# 5_64MB_SDRAM.net
KiCad netlist of a schematic drawn in Altium Designer
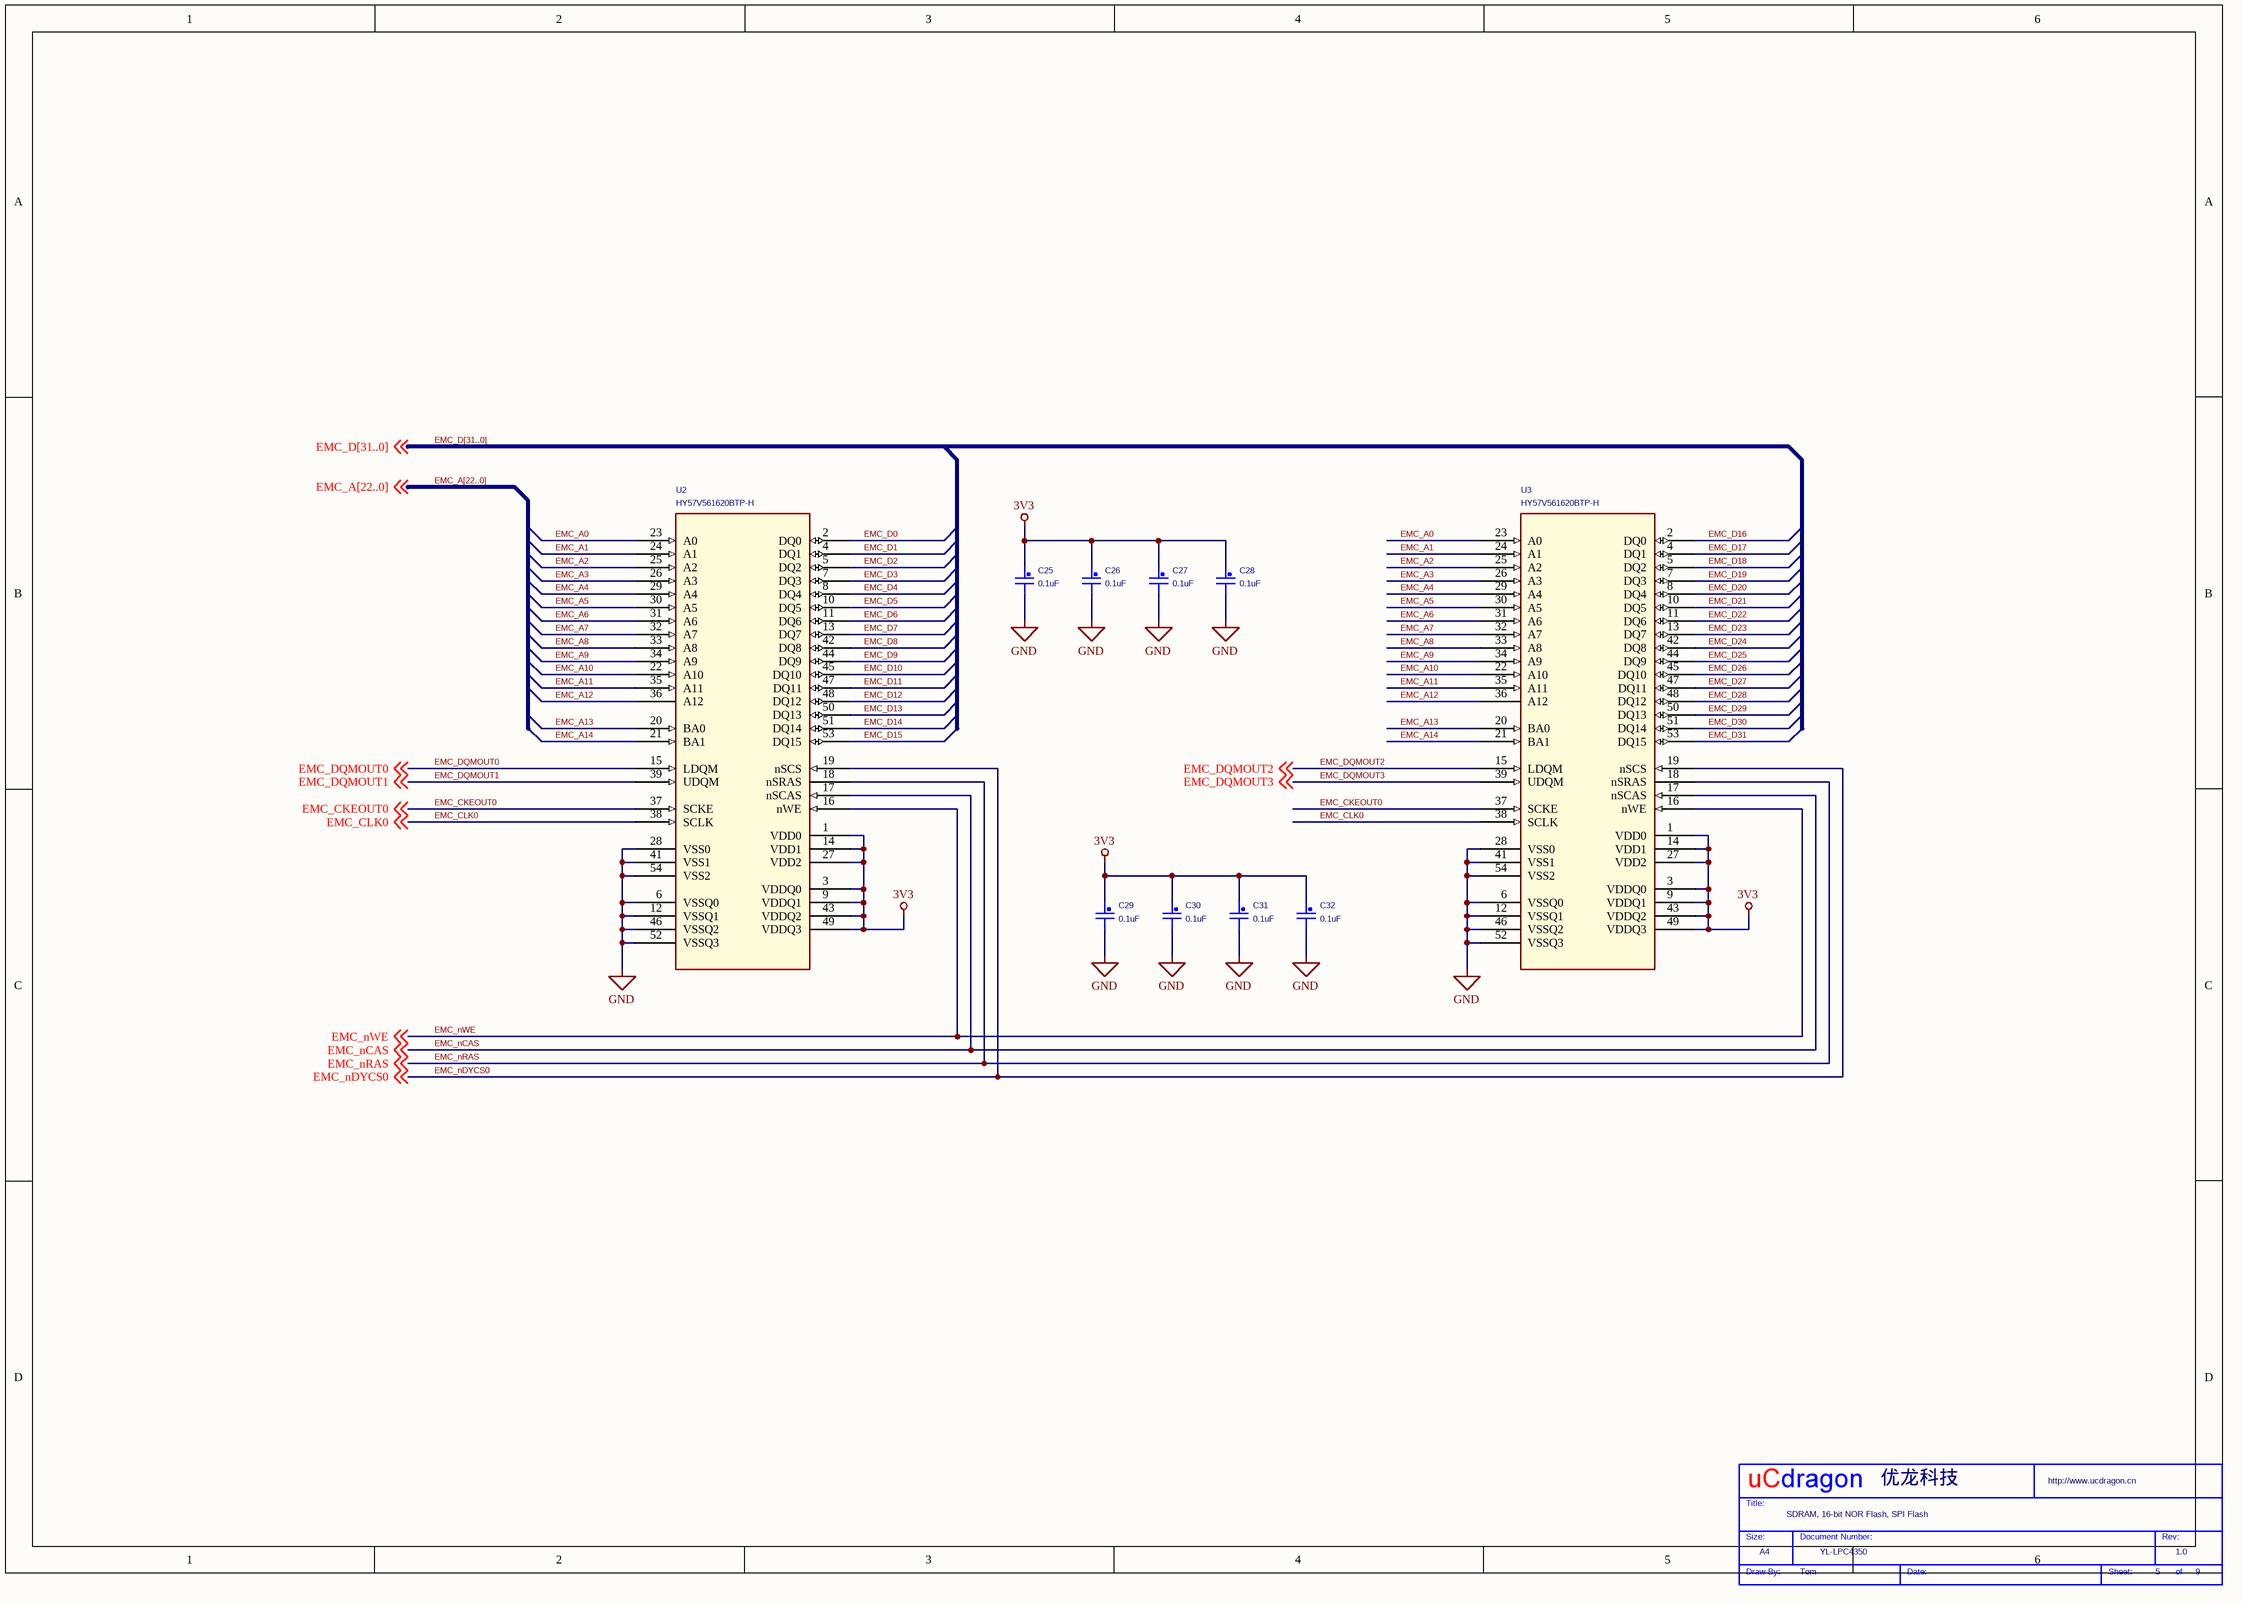
[diagram p0: 5) 64MB SDRAM.SchDoc]

(export (version "E")
  (design (tool "Eeschema 10.0.6"))
  (components
    (comp (ref "C25")
      (value "0.1uF")
      (footprint "CAP0805")
      (fields (field (name "VOLTAGE") "16V"))
      (libsource (lib "*") (part "C_Generic"))
    )
    (comp (ref "C26")
      (value "0.1uF")
      (footprint "CAP0805")
      (fields (field (name "VOLTAGE") "16V"))
      (libsource (lib "*") (part "C_Generic"))
    )
    (comp (ref "C27")
      (value "0.1uF")
      (footprint "CAP0805")
      (fields (field (name "VOLTAGE") "16V"))
      (libsource (lib "*") (part "C_Generic"))
    )
    (comp (ref "C28")
      (value "0.1uF")
      (footprint "CAP0805")
      (fields (field (name "VOLTAGE") "16V"))
      (libsource (lib "*") (part "C_Generic"))
    )
    (comp (ref "C29")
      (value "0.1uF")
      (footprint "CAP0805")
      (fields (field (name "VOLTAGE") "16V"))
      (libsource (lib "*") (part "C_Generic"))
    )
    (comp (ref "C30")
      (value "0.1uF")
      (footprint "CAP0805")
      (fields (field (name "VOLTAGE") "16V"))
      (libsource (lib "*") (part "C_Generic"))
    )
    (comp (ref "C31")
      (value "0.1uF")
      (footprint "CAP0805")
      (fields (field (name "VOLTAGE") "16V"))
      (libsource (lib "*") (part "C_Generic"))
    )
    (comp (ref "C32")
      (value "0.1uF")
      (footprint "CAP0805")
      (fields (field (name "VOLTAGE") "16V"))
      (libsource (lib "*") (part "C_Generic"))
    )
    (comp (ref "U2") (value "HY57V561620BTP-H") (libsource (lib "*") (part "K4S561632C")))
    (comp (ref "U3") (value "HY57V561620BTP-H") (libsource (lib "*") (part "K4S561632C")))
  )
  (nets
    (net (code "1") (name "3V3") (class "Default")
      (node (ref "C25") (pin "1") (pinfunction "1_1") (pintype "passive"))
      (node (ref "C26") (pin "1") (pinfunction "1_1") (pintype "passive"))
      (node (ref "C27") (pin "1") (pinfunction "1_1") (pintype "passive"))
      (node (ref "C28") (pin "1") (pinfunction "1_1") (pintype "passive"))
      (node (ref "C29") (pin "1") (pinfunction "1_1") (pintype "passive"))
      (node (ref "C30") (pin "1") (pinfunction "1_1") (pintype "passive"))
      (node (ref "C31") (pin "1") (pinfunction "1_1") (pintype "passive"))
      (node (ref "C32") (pin "1") (pinfunction "1_1") (pintype "passive"))
      (node (ref "U2") (pin "1") (pinfunction "VDD0_1") (pintype "power_in"))
      (node (ref "U2") (pin "14") (pinfunction "VDD1_14") (pintype "power_in"))
      (node (ref "U2") (pin "27") (pinfunction "VDD2_27") (pintype "power_in"))
      (node (ref "U2") (pin "3") (pinfunction "VDDQ0_3") (pintype "power_in"))
      (node (ref "U2") (pin "43") (pinfunction "VDDQ2_43") (pintype "power_in"))
      (node (ref "U2") (pin "49") (pinfunction "VDDQ3_49") (pintype "power_in"))
      (node (ref "U2") (pin "9") (pinfunction "VDDQ1_9") (pintype "power_in"))
      (node (ref "U3") (pin "1") (pinfunction "VDD0_1") (pintype "power_in"))
      (node (ref "U3") (pin "14") (pinfunction "VDD1_14") (pintype "power_in"))
      (node (ref "U3") (pin "27") (pinfunction "VDD2_27") (pintype "power_in"))
      (node (ref "U3") (pin "3") (pinfunction "VDDQ0_3") (pintype "power_in"))
      (node (ref "U3") (pin "43") (pinfunction "VDDQ2_43") (pintype "power_in"))
      (node (ref "U3") (pin "49") (pinfunction "VDDQ3_49") (pintype "power_in"))
      (node (ref "U3") (pin "9") (pinfunction "VDDQ1_9") (pintype "power_in"))
    )
    (net (code "2") (name "EMC_A0") (class "Default")
      (node (ref "U2") (pin "23") (pinfunction "A0_23") (pintype "input"))
      (node (ref "U3") (pin "23") (pinfunction "A0_23") (pintype "input"))
    )
    (net (code "3") (name "EMC_A1") (class "Default")
      (node (ref "U2") (pin "24") (pinfunction "A1_24") (pintype "input"))
      (node (ref "U3") (pin "24") (pinfunction "A1_24") (pintype "input"))
    )
    (net (code "4") (name "EMC_A2") (class "Default")
      (node (ref "U2") (pin "25") (pinfunction "A2_25") (pintype "input"))
      (node (ref "U3") (pin "25") (pinfunction "A2_25") (pintype "input"))
    )
    (net (code "5") (name "EMC_A3") (class "Default")
      (node (ref "U2") (pin "26") (pinfunction "A3_26") (pintype "input"))
      (node (ref "U3") (pin "26") (pinfunction "A3_26") (pintype "input"))
    )
    (net (code "6") (name "EMC_A4") (class "Default")
      (node (ref "U2") (pin "29") (pinfunction "A4_29") (pintype "input"))
      (node (ref "U3") (pin "29") (pinfunction "A4_29") (pintype "input"))
    )
    (net (code "7") (name "EMC_A5") (class "Default")
      (node (ref "U2") (pin "30") (pinfunction "A5_30") (pintype "input"))
      (node (ref "U3") (pin "30") (pinfunction "A5_30") (pintype "input"))
    )
    (net (code "8") (name "EMC_A6") (class "Default")
      (node (ref "U2") (pin "31") (pinfunction "A6_31") (pintype "input"))
      (node (ref "U3") (pin "31") (pinfunction "A6_31") (pintype "input"))
    )
    (net (code "9") (name "EMC_A7") (class "Default")
      (node (ref "U2") (pin "32") (pinfunction "A7_32") (pintype "input"))
      (node (ref "U3") (pin "32") (pinfunction "A7_32") (pintype "input"))
    )
    (net (code "10") (name "EMC_A8") (class "Default")
      (node (ref "U2") (pin "33") (pinfunction "A8_33") (pintype "input"))
      (node (ref "U3") (pin "33") (pinfunction "A8_33") (pintype "input"))
    )
    (net (code "11") (name "EMC_A9") (class "Default")
      (node (ref "U2") (pin "34") (pinfunction "A9_34") (pintype "input"))
      (node (ref "U3") (pin "34") (pinfunction "A9_34") (pintype "input"))
    )
    (net (code "12") (name "EMC_A10") (class "Default")
      (node (ref "U2") (pin "22") (pinfunction "A10_22") (pintype "input"))
      (node (ref "U3") (pin "22") (pinfunction "A10_22") (pintype "input"))
    )
    (net (code "13") (name "EMC_A11") (class "Default")
      (node (ref "U2") (pin "35") (pinfunction "A11_35") (pintype "input"))
      (node (ref "U3") (pin "35") (pinfunction "A11_35") (pintype "input"))
    )
    (net (code "14") (name "EMC_A12") (class "Default")
      (node (ref "U2") (pin "36") (pinfunction "A12_36") (pintype "passive"))
      (node (ref "U3") (pin "36") (pinfunction "A12_36") (pintype "passive"))
    )
    (net (code "15") (name "EMC_A13") (class "Default")
      (node (ref "U2") (pin "20") (pinfunction "BA0_20") (pintype "input"))
      (node (ref "U3") (pin "20") (pinfunction "BA0_20") (pintype "input"))
    )
    (net (code "16") (name "EMC_A14") (class "Default")
      (node (ref "U2") (pin "21") (pinfunction "BA1_21") (pintype "input"))
      (node (ref "U3") (pin "21") (pinfunction "BA1_21") (pintype "input"))
    )
    (net (code "18") (name "EMC_CKEOUT0") (class "Default")
      (node (ref "U2") (pin "37") (pinfunction "SCKE_37") (pintype "input"))
      (node (ref "U3") (pin "37") (pinfunction "SCKE_37") (pintype "input"))
    )
    (net (code "19") (name "EMC_CLK0") (class "Default")
      (node (ref "U2") (pin "38") (pinfunction "SCLK_38") (pintype "input"))
      (node (ref "U3") (pin "38") (pinfunction "SCLK_38") (pintype "input"))
    )
    (net (code "20") (name "EMC_D0") (class "Default")
      (node (ref "U2") (pin "2") (pinfunction "DQ0_2") (pintype "bidirectional"))
    )
    (net (code "21") (name "EMC_D1") (class "Default")
      (node (ref "U2") (pin "4") (pinfunction "DQ1_4") (pintype "bidirectional"))
    )
    (net (code "22") (name "EMC_D2") (class "Default")
      (node (ref "U2") (pin "5") (pinfunction "DQ2_5") (pintype "bidirectional"))
    )
    (net (code "23") (name "EMC_D3") (class "Default")
      (node (ref "U2") (pin "7") (pinfunction "DQ3_7") (pintype "bidirectional"))
    )
    (net (code "24") (name "EMC_D4") (class "Default")
      (node (ref "U2") (pin "8") (pinfunction "DQ4_8") (pintype "bidirectional"))
    )
    (net (code "25") (name "EMC_D5") (class "Default")
      (node (ref "U2") (pin "10") (pinfunction "DQ5_10") (pintype "bidirectional"))
    )
    (net (code "26") (name "EMC_D6") (class "Default")
      (node (ref "U2") (pin "11") (pinfunction "DQ6_11") (pintype "bidirectional"))
    )
    (net (code "27") (name "EMC_D7") (class "Default")
      (node (ref "U2") (pin "13") (pinfunction "DQ7_13") (pintype "bidirectional"))
    )
    (net (code "28") (name "EMC_D8") (class "Default")
      (node (ref "U2") (pin "42") (pinfunction "DQ8_42") (pintype "bidirectional"))
    )
    (net (code "29") (name "EMC_D9") (class "Default")
      (node (ref "U2") (pin "44") (pinfunction "DQ9_44") (pintype "bidirectional"))
    )
    (net (code "30") (name "EMC_D10") (class "Default")
      (node (ref "U2") (pin "45") (pinfunction "DQ10_45") (pintype "bidirectional"))
    )
    (net (code "31") (name "EMC_D11") (class "Default")
      (node (ref "U2") (pin "47") (pinfunction "DQ11_47") (pintype "bidirectional"))
    )
    (net (code "32") (name "EMC_D12") (class "Default")
      (node (ref "U2") (pin "48") (pinfunction "DQ12_48") (pintype "bidirectional"))
    )
    (net (code "33") (name "EMC_D13") (class "Default")
      (node (ref "U2") (pin "50") (pinfunction "DQ13_50") (pintype "bidirectional"))
    )
    (net (code "34") (name "EMC_D14") (class "Default")
      (node (ref "U2") (pin "51") (pinfunction "DQ14_51") (pintype "bidirectional"))
    )
    (net (code "35") (name "EMC_D15") (class "Default")
      (node (ref "U2") (pin "53") (pinfunction "DQ15_53") (pintype "bidirectional"))
    )
    (net (code "36") (name "EMC_D16") (class "Default")
      (node (ref "U3") (pin "2") (pinfunction "DQ0_2") (pintype "bidirectional"))
    )
    (net (code "37") (name "EMC_D17") (class "Default")
      (node (ref "U3") (pin "4") (pinfunction "DQ1_4") (pintype "bidirectional"))
    )
    (net (code "38") (name "EMC_D18") (class "Default")
      (node (ref "U3") (pin "5") (pinfunction "DQ2_5") (pintype "bidirectional"))
    )
    (net (code "39") (name "EMC_D19") (class "Default")
      (node (ref "U3") (pin "7") (pinfunction "DQ3_7") (pintype "bidirectional"))
    )
    (net (code "40") (name "EMC_D20") (class "Default")
      (node (ref "U3") (pin "8") (pinfunction "DQ4_8") (pintype "bidirectional"))
    )
    (net (code "41") (name "EMC_D21") (class "Default")
      (node (ref "U3") (pin "10") (pinfunction "DQ5_10") (pintype "bidirectional"))
    )
    (net (code "42") (name "EMC_D22") (class "Default")
      (node (ref "U3") (pin "11") (pinfunction "DQ6_11") (pintype "bidirectional"))
    )
    (net (code "43") (name "EMC_D23") (class "Default")
      (node (ref "U3") (pin "13") (pinfunction "DQ7_13") (pintype "bidirectional"))
    )
    (net (code "44") (name "EMC_D24") (class "Default")
      (node (ref "U3") (pin "42") (pinfunction "DQ8_42") (pintype "bidirectional"))
    )
    (net (code "45") (name "EMC_D25") (class "Default")
      (node (ref "U3") (pin "44") (pinfunction "DQ9_44") (pintype "bidirectional"))
    )
    (net (code "46") (name "EMC_D26") (class "Default")
      (node (ref "U3") (pin "45") (pinfunction "DQ10_45") (pintype "bidirectional"))
    )
    (net (code "47") (name "EMC_D27") (class "Default")
      (node (ref "U3") (pin "47") (pinfunction "DQ11_47") (pintype "bidirectional"))
    )
    (net (code "48") (name "EMC_D28") (class "Default")
      (node (ref "U3") (pin "48") (pinfunction "DQ12_48") (pintype "bidirectional"))
    )
    (net (code "49") (name "EMC_D29") (class "Default")
      (node (ref "U3") (pin "50") (pinfunction "DQ13_50") (pintype "bidirectional"))
    )
    (net (code "50") (name "EMC_D30") (class "Default")
      (node (ref "U3") (pin "51") (pinfunction "DQ14_51") (pintype "bidirectional"))
    )
    (net (code "51") (name "EMC_D31") (class "Default")
      (node (ref "U3") (pin "53") (pinfunction "DQ15_53") (pintype "bidirectional"))
    )
    (net (code "52") (name "EMC_DQMOUT0") (class "Default")
      (node (ref "U2") (pin "15") (pinfunction "LDQM_15") (pintype "input"))
    )
    (net (code "53") (name "EMC_DQMOUT1") (class "Default")
      (node (ref "U2") (pin "39") (pinfunction "UDQM_39") (pintype "input"))
    )
    (net (code "54") (name "EMC_DQMOUT2") (class "Default")
      (node (ref "U3") (pin "15") (pinfunction "LDQM_15") (pintype "input"))
    )
    (net (code "55") (name "EMC_DQMOUT3") (class "Default")
      (node (ref "U3") (pin "39") (pinfunction "UDQM_39") (pintype "input"))
    )
    (net (code "57") (name "EMC_nCAS") (class "Default")
      (node (ref "U2") (pin "17") (pinfunction "nSCAS_17") (pintype "input"))
      (node (ref "U3") (pin "17") (pinfunction "nSCAS_17") (pintype "input"))
    )
    (net (code "58") (name "EMC_nDYCS0") (class "Default")
      (node (ref "U2") (pin "19") (pinfunction "nSCS_19") (pintype "input"))
      (node (ref "U3") (pin "19") (pinfunction "nSCS_19") (pintype "input"))
    )
    (net (code "59") (name "EMC_nRAS") (class "Default")
      (node (ref "U2") (pin "18") (pinfunction "nSRAS_18") (pintype "passive"))
      (node (ref "U3") (pin "18") (pinfunction "nSRAS_18") (pintype "passive"))
    )
    (net (code "60") (name "EMC_nWE") (class "Default")
      (node (ref "U2") (pin "16") (pinfunction "nWE_16") (pintype "input"))
      (node (ref "U3") (pin "16") (pinfunction "nWE_16") (pintype "input"))
    )
    (net (code "61") (name "GND") (class "Default")
      (node (ref "C25") (pin "2") (pinfunction "2_2") (pintype "passive"))
      (node (ref "C26") (pin "2") (pinfunction "2_2") (pintype "passive"))
      (node (ref "C27") (pin "2") (pinfunction "2_2") (pintype "passive"))
      (node (ref "C28") (pin "2") (pinfunction "2_2") (pintype "passive"))
      (node (ref "C29") (pin "2") (pinfunction "2_2") (pintype "passive"))
      (node (ref "C30") (pin "2") (pinfunction "2_2") (pintype "passive"))
      (node (ref "C31") (pin "2") (pinfunction "2_2") (pintype "passive"))
      (node (ref "C32") (pin "2") (pinfunction "2_2") (pintype "passive"))
      (node (ref "U2") (pin "12") (pinfunction "VSSQ1_12") (pintype "power_in"))
      (node (ref "U2") (pin "28") (pinfunction "VSS0_28") (pintype "power_in"))
      (node (ref "U2") (pin "41") (pinfunction "VSS1_41") (pintype "power_in"))
      (node (ref "U2") (pin "46") (pinfunction "VSSQ2_46") (pintype "power_in"))
      (node (ref "U2") (pin "52") (pinfunction "VSSQ3_52") (pintype "power_in"))
      (node (ref "U2") (pin "54") (pinfunction "VSS2_54") (pintype "power_in"))
      (node (ref "U2") (pin "6") (pinfunction "VSSQ0_6") (pintype "power_in"))
      (node (ref "U3") (pin "12") (pinfunction "VSSQ1_12") (pintype "power_in"))
      (node (ref "U3") (pin "28") (pinfunction "VSS0_28") (pintype "power_in"))
      (node (ref "U3") (pin "41") (pinfunction "VSS1_41") (pintype "power_in"))
      (node (ref "U3") (pin "46") (pinfunction "VSSQ2_46") (pintype "power_in"))
      (node (ref "U3") (pin "52") (pinfunction "VSSQ3_52") (pintype "power_in"))
      (node (ref "U3") (pin "54") (pinfunction "VSS2_54") (pintype "power_in"))
      (node (ref "U3") (pin "6") (pinfunction "VSSQ0_6") (pintype "power_in"))
    )
  )
)
